# WL_PGA_ATT.net
KiCad netlist of a schematic drawn in Altium Designer
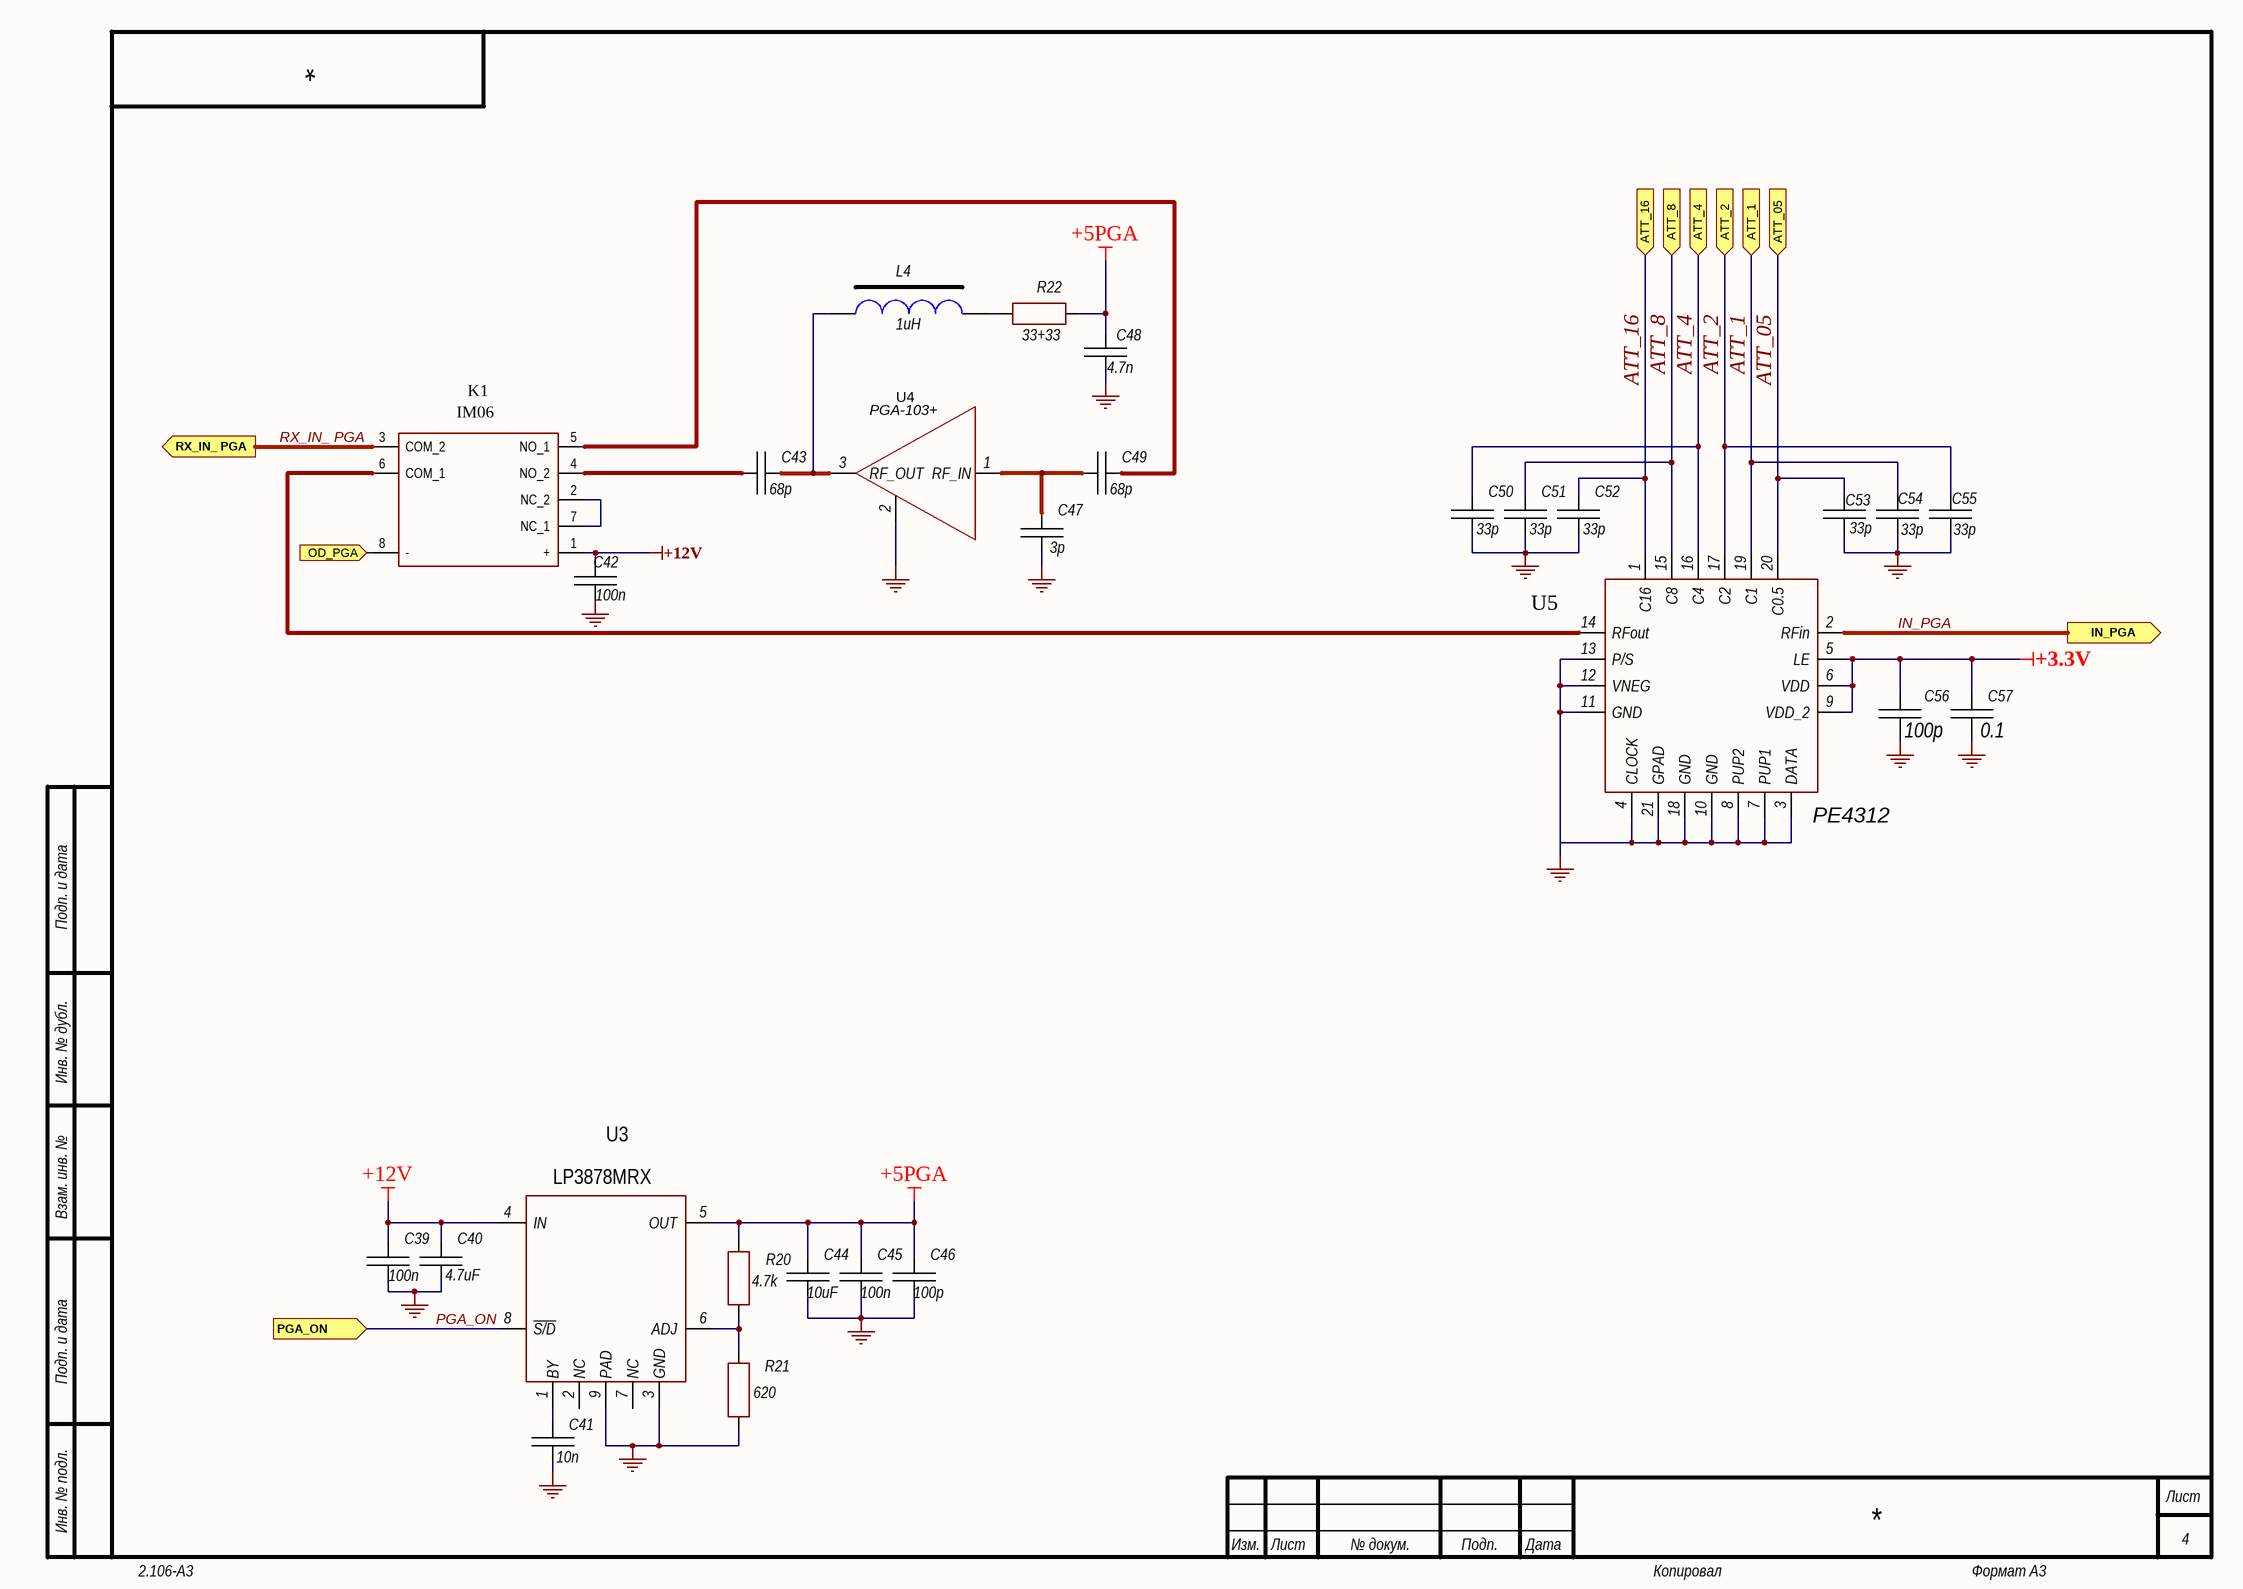
[diagram p0: WL_PGA_ATT.SchDoc]

(export (version "E")
  (design (tool "Eeschema 10.0.6"))
  (components
    (comp (ref "C39")
      (value "100n")
      (footprint "standard:CH0805C")
      (libsource (lib "Discrete") (part "Capacitor"))
    )
    (comp (ref "C40")
      (value "4.7uF")
      (footprint "standard:CH0805C")
      (libsource (lib "Discrete") (part "Capacitor"))
    )
    (comp (ref "C41")
      (value "10n")
      (footprint "standard:CH0805C")
      (libsource (lib "Discrete") (part "Capacitor"))
    )
    (comp (ref "C42")
      (value "100n")
      (footprint "standard:CH0805C")
      (libsource (lib "Discrete") (part "Capacitor"))
    )
    (comp (ref "C43")
      (value "68p")
      (footprint "standard:CH0805C")
      (libsource (lib "Discrete") (part "Capacitor"))
    )
    (comp (ref "C44")
      (value "10uF")
      (footprint "standard:CH0805C")
      (libsource (lib "Discrete") (part "Capacitor"))
    )
    (comp (ref "C45")
      (value "100n")
      (footprint "standard:CH0805C")
      (libsource (lib "Discrete") (part "Capacitor"))
    )
    (comp (ref "C46")
      (value "100p")
      (footprint "standard:CH0805C")
      (libsource (lib "Discrete") (part "Capacitor"))
    )
    (comp (ref "C47")
      (value "3p")
      (footprint "standard:CH0805C")
      (libsource (lib "Discrete") (part "Capacitor"))
    )
    (comp (ref "C48")
      (value "4.7n")
      (footprint "standard:CH0805C")
      (libsource (lib "Discrete") (part "Capacitor"))
    )
    (comp (ref "C49")
      (value "68p")
      (footprint "standard:CH0805C")
      (libsource (lib "Discrete") (part "Capacitor"))
    )
    (comp (ref "C50")
      (value "33p")
      (footprint "standard:CH0603C")
      (libsource (lib "Discrete") (part "Capacitor"))
    )
    (comp (ref "C51")
      (value "33p")
      (footprint "standard:CH0603C")
      (libsource (lib "Discrete") (part "Capacitor"))
    )
    (comp (ref "C52")
      (value "33p")
      (footprint "standard:CH0603C")
      (libsource (lib "Discrete") (part "Capacitor"))
    )
    (comp (ref "C53")
      (value "33p")
      (footprint "standard:CH0603C")
      (libsource (lib "Discrete") (part "Capacitor"))
    )
    (comp (ref "C54")
      (value "33p")
      (footprint "standard:CH0603C")
      (libsource (lib "Discrete") (part "Capacitor"))
    )
    (comp (ref "C55")
      (value "33p")
      (footprint "standard:CH0603C")
      (libsource (lib "Discrete") (part "Capacitor"))
    )
    (comp (ref "C56")
      (value "100p")
      (footprint "standard:CH0805C")
      (libsource (lib "Discrete") (part "Capacitor"))
    )
    (comp (ref "C57")
      (value "0.1")
      (footprint "standard:CH0805C")
      (libsource (lib "Discrete") (part "Capacitor"))
    )
    (comp (ref "K1") (value "IM06") (footprint "IM06") (libsource (lib "Relay") (part "IM06-V1")))
    (comp (ref "L4") (value "1uH") (footprint "L1210") (libsource (lib "Transformers") (part "TRANS")))
    (comp (ref "R20") (value "4.7k") (footprint "standard:CH0805R") (libsource (lib "") (part "Resistor_1")))
    (comp (ref "R21") (value "620") (footprint "standard:CH0805R") (libsource (lib "") (part "Resistor_1")))
    (comp (ref "R22")
      (value "33+33")
      (footprint "WL_RFFC:CH1206R")
      (libsource (lib "Discrete") (part "Resistor"))
    )
    (comp (ref "U3")
      (value "LP3878MRX")
      (footprint "8-SOIC (PAD)")
      (libsource (lib "Power Supplies") (part "LP3878"))
    )
    (comp (ref "U4") (value "PGA-103+") (footprint "SOT89_123") (libsource (lib "Digital") (part "PGA-103+")))
    (comp (ref "U5") (value "PE4312") (footprint "20-QFN (4x4)") (libsource (lib "Digital") (part "PE4302")))
  )
  (nets
    (net (code "1") (name "+3.3V") (class "Default")
      (node (ref "C56") (pin "1") (pinfunction "1_1") (pintype "passive"))
      (node (ref "C57") (pin "1") (pinfunction "1_1") (pintype "passive"))
      (node (ref "U5") (pin "5") (pinfunction "LE_5") (pintype "passive"))
      (node (ref "U5") (pin "6") (pinfunction "VDD_6") (pintype "passive"))
      (node (ref "U5") (pin "9") (pinfunction "VDD_2_9") (pintype "passive"))
    )
    (net (code "2") (name "+5PGA") (class "Default")
      (node (ref "C44") (pin "2") (pinfunction "2_2") (pintype "passive"))
      (node (ref "C45") (pin "2") (pinfunction "2_2") (pintype "passive"))
      (node (ref "C46") (pin "2") (pinfunction "2_2") (pintype "passive"))
      (node (ref "C48") (pin "2") (pinfunction "2_2") (pintype "passive"))
      (node (ref "R20") (pin "2") (pinfunction "2_2") (pintype "passive"))
      (node (ref "R22") (pin "2") (pinfunction "2_2") (pintype "passive"))
      (node (ref "U3") (pin "5") (pinfunction "OUT_5") (pintype "power_in"))
    )
    (net (code "3") (name "+12V") (class "Default")
      (node (ref "C39") (pin "2") (pinfunction "2_2") (pintype "passive"))
      (node (ref "C40") (pin "2") (pinfunction "2_2") (pintype "passive"))
      (node (ref "C42") (pin "2") (pinfunction "2_2") (pintype "passive"))
      (node (ref "K1") (pin "1") (pinfunction "+_1") (pintype "passive"))
      (node (ref "U3") (pin "4") (pinfunction "IN_4") (pintype "power_in"))
    )
    (net (code "4") (name "/ATT_1") (class "Default")
      (node (ref "C54") (pin "2") (pinfunction "2_2") (pintype "passive"))
      (node (ref "U5") (pin "19") (pinfunction "C1_19") (pintype "passive"))
    )
    (net (code "5") (name "/ATT_2") (class "Default")
      (node (ref "C55") (pin "2") (pinfunction "2_2") (pintype "passive"))
      (node (ref "U5") (pin "17") (pinfunction "C2_17") (pintype "passive"))
    )
    (net (code "6") (name "/ATT_4") (class "Default")
      (node (ref "C50") (pin "2") (pinfunction "2_2") (pintype "passive"))
      (node (ref "U5") (pin "16") (pinfunction "C4_16") (pintype "passive"))
    )
    (net (code "7") (name "/ATT_05") (class "Default")
      (node (ref "C53") (pin "2") (pinfunction "2_2") (pintype "passive"))
      (node (ref "U5") (pin "20") (pinfunction "C0.5_20") (pintype "passive"))
    )
    (net (code "8") (name "/ATT_8") (class "Default")
      (node (ref "C51") (pin "2") (pinfunction "2_2") (pintype "passive"))
      (node (ref "U5") (pin "15") (pinfunction "C8_15") (pintype "passive"))
    )
    (net (code "9") (name "/ATT_16") (class "Default")
      (node (ref "C52") (pin "2") (pinfunction "2_2") (pintype "passive"))
      (node (ref "U5") (pin "1") (pinfunction "C16_1") (pintype "passive"))
    )
    (net (code "10") (name "/IN_PGA") (class "Default")
      (node (ref "U5") (pin "2") (pinfunction "RFin_2") (pintype "passive"))
    )
    (net (code "11") (name "/OD_PGA") (class "Default")
      (node (ref "K1") (pin "8") (pinfunction "-_8") (pintype "passive"))
    )
    (net (code "12") (name "/PGA_ON") (class "Default")
      (node (ref "U3") (pin "8") (pinfunction "~{S/D}_8") (pintype "power_in"))
    )
    (net (code "13") (name "/RX_IN_ PGA") (class "Default")
      (node (ref "K1") (pin "3") (pinfunction "COM_2_3") (pintype "passive"))
    )
    (net (code "14") (name "GND") (class "Default")
      (node (ref "C39") (pin "1") (pinfunction "1_1") (pintype "passive"))
      (node (ref "C40") (pin "1") (pinfunction "1_1") (pintype "passive"))
      (node (ref "C41") (pin "1") (pinfunction "1_1") (pintype "passive"))
      (node (ref "C42") (pin "1") (pinfunction "1_1") (pintype "passive"))
      (node (ref "C44") (pin "1") (pinfunction "1_1") (pintype "passive"))
      (node (ref "C45") (pin "1") (pinfunction "1_1") (pintype "passive"))
      (node (ref "C46") (pin "1") (pinfunction "1_1") (pintype "passive"))
      (node (ref "C47") (pin "1") (pinfunction "1_1") (pintype "passive"))
      (node (ref "C48") (pin "1") (pinfunction "1_1") (pintype "passive"))
      (node (ref "C50") (pin "1") (pinfunction "1_1") (pintype "passive"))
      (node (ref "C51") (pin "1") (pinfunction "1_1") (pintype "passive"))
      (node (ref "C52") (pin "1") (pinfunction "1_1") (pintype "passive"))
      (node (ref "C53") (pin "1") (pinfunction "1_1") (pintype "passive"))
      (node (ref "C54") (pin "1") (pinfunction "1_1") (pintype "passive"))
      (node (ref "C55") (pin "1") (pinfunction "1_1") (pintype "passive"))
      (node (ref "C56") (pin "2") (pinfunction "2_2") (pintype "passive"))
      (node (ref "C57") (pin "2") (pinfunction "2_2") (pintype "passive"))
      (node (ref "R21") (pin "1") (pinfunction "1_1") (pintype "passive"))
      (node (ref "U3") (pin "3") (pinfunction "GND_3") (pintype "passive"))
      (node (ref "U3") (pin "9") (pinfunction "PAD_9") (pintype "passive"))
      (node (ref "U4") (pin "2") (pinfunction "GND_2") (pintype "passive"))
      (node (ref "U5") (pin "10") (pinfunction "GND_10") (pintype "passive"))
      (node (ref "U5") (pin "11") (pinfunction "GND_11") (pintype "passive"))
      (node (ref "U5") (pin "12") (pinfunction "VNEG_12") (pintype "passive"))
      (node (ref "U5") (pin "13") (pinfunction "P/S_13") (pintype "passive"))
      (node (ref "U5") (pin "18") (pinfunction "GND_18") (pintype "passive"))
      (node (ref "U5") (pin "21") (pinfunction "GPAD_21") (pintype "passive"))
      (node (ref "U5") (pin "3") (pinfunction "DATA_3") (pintype "passive"))
      (node (ref "U5") (pin "4") (pinfunction "CLOCK_4") (pintype "passive"))
      (node (ref "U5") (pin "7") (pinfunction "PUP1_7") (pintype "passive"))
      (node (ref "U5") (pin "8") (pinfunction "PUP2_8") (pintype "passive"))
    )
    (net (code "15") (name "Net-(K1-COM_1)") (class "Default")
      (node (ref "K1") (pin "6") (pinfunction "COM_1_6") (pintype "passive"))
      (node (ref "U5") (pin "14") (pinfunction "RFout_14") (pintype "passive"))
    )
    (net (code "16") (name "Net-(K1-NC_1)") (class "Default")
      (node (ref "K1") (pin "2") (pinfunction "NC_2_2") (pintype "passive"))
      (node (ref "K1") (pin "7") (pinfunction "NC_1_7") (pintype "passive"))
    )
    (net (code "17") (name "Net-(K1-NO_1)") (class "Default")
      (node (ref "C49") (pin "2") (pinfunction "2_2") (pintype "passive"))
      (node (ref "K1") (pin "5") (pinfunction "NO_1_5") (pintype "passive"))
    )
    (net (code "18") (name "Net-(K1-NO_2)") (class "Default")
      (node (ref "C43") (pin "1") (pinfunction "1_1") (pintype "passive"))
      (node (ref "K1") (pin "4") (pinfunction "NO_2_4") (pintype "passive"))
    )
    (net (code "19") (name "Net-(L4-Pad1)") (class "Default")
      (node (ref "L4") (pin "1") (pinfunction "1_1") (pintype "power_in"))
      (node (ref "R22") (pin "1") (pinfunction "1_1") (pintype "passive"))
    )
    (net (code "20") (name "Net-(U3-ADJ)") (class "Default")
      (node (ref "R20") (pin "1") (pinfunction "1_1") (pintype "passive"))
      (node (ref "R21") (pin "2") (pinfunction "2_2") (pintype "passive"))
      (node (ref "U3") (pin "6") (pinfunction "ADJ_6") (pintype "passive"))
    )
    (net (code "21") (name "Net-(U3-BY)") (class "Default")
      (node (ref "C41") (pin "2") (pinfunction "2_2") (pintype "passive"))
      (node (ref "U3") (pin "1") (pinfunction "BY_1") (pintype "passive"))
    )
    (net (code "22") (name "Net-(U4-RF_IN)") (class "Default")
      (node (ref "C47") (pin "2") (pinfunction "2_2") (pintype "passive"))
      (node (ref "C49") (pin "1") (pinfunction "1_1") (pintype "passive"))
      (node (ref "U4") (pin "1") (pinfunction "RF_IN_1") (pintype "passive"))
    )
    (net (code "23") (name "Net-(U4-RF_OUT)") (class "Default")
      (node (ref "C43") (pin "2") (pinfunction "2_2") (pintype "passive"))
      (node (ref "L4") (pin "2") (pinfunction "2_2") (pintype "power_in"))
      (node (ref "U4") (pin "3") (pinfunction "RF_OUT_3") (pintype "passive"))
    )
    (net (code "24") (name "unconnected-(U3-NC-Pad2)") (class "Default")
      (node (ref "U3") (pin "2") (pinfunction "NC_2") (pintype "passive"))
    )
    (net (code "25") (name "unconnected-(U3-NC-Pad7)") (class "Default")
      (node (ref "U3") (pin "7") (pinfunction "NC_7") (pintype "passive"))
    )
  )
)
